# Schematic_v1_1_v8.net
KiCad netlist of a schematic drawn in EAGLE
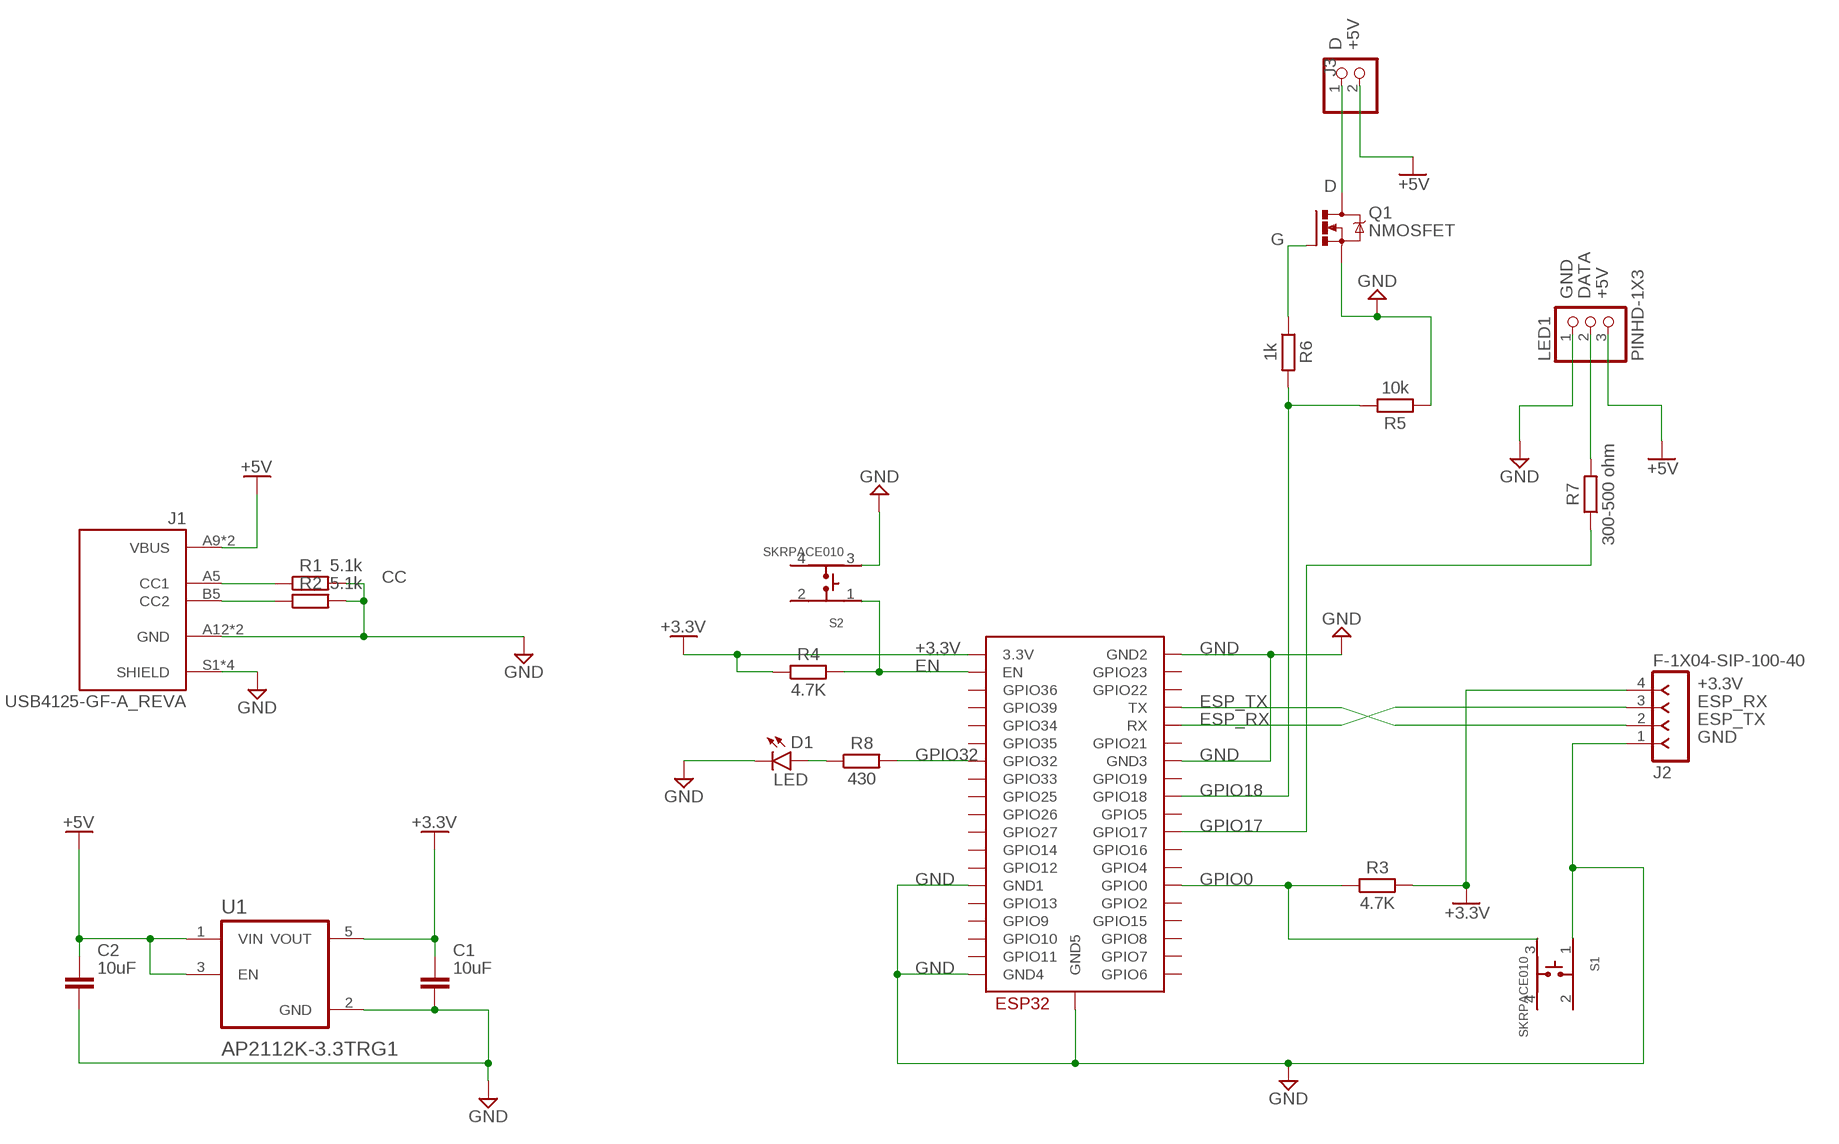
[diagram p0: schematic, sheet 1]

(export (version "E")
  (design (tool "Eeschema 10.0.6"))
  (components
    (comp (ref "C1")
      (value "10uF")
      (footprint "eagle-import:CAPC1608X85")
      (libsource (lib "eagle-import") (part "CCHIP-0603(1608-METRIC)_"))
    )
    (comp (ref "C2")
      (value "10uF")
      (footprint "eagle-import:CAPC1608X85")
      (libsource (lib "eagle-import") (part "CCHIP-0603(1608-METRIC)_"))
    )
    (comp (ref "D1")
      (value "LED")
      (footprint "eagle-import:LEDC1608X80N_FLAT-R")
      (libsource (lib "eagle-import") (part "CHIP-FLAT-R_0603-0.80MM"))
    )
    (comp (ref "J1")
      (value "USB4125-GF-A_REVA")
      (footprint "eagle-import:GCT_USB4125-GF-A_REVA")
      (fields (field (name "MF") "Global Connector Technology") (field (name "MP") "USB4125-GF-A"))
      (libsource (lib "eagle-import") (part "USB4125-GF-A_REVA"))
    )
    (comp (ref "J2")
      (value "F-1X04-SIP-100-40")
      (footprint "eagle-import:SIP-100-04-40")
      (libsource (lib "eagle-import") (part "F-1X04-SIP-100-40"))
    )
    (comp (ref "J3")
      (value "PINHD-1X2")
      (footprint "eagle-import:1X02")
      (libsource (lib "eagle-import") (part "PINHD-1X2"))
    )
    (comp (ref "LED1")
      (value "PINHD-1X3")
      (footprint "eagle-import:1X03")
      (libsource (lib "eagle-import") (part "PINHD-1X3"))
    )
    (comp (ref "Q1")
      (value "NMOSFET")
      (footprint "eagle-import:SOT23")
      (libsource (lib "eagle-import") (part "NMOSFETSOT23_"))
    )
    (comp (ref "R1")
      (value "5.1k")
      (footprint "eagle-import:RESC1608X60")
      (libsource (lib "eagle-import") (part "RCHIP-0603(1608-METRIC)_"))
    )
    (comp (ref "R2")
      (value "5.1k")
      (footprint "eagle-import:RESC1608X60")
      (libsource (lib "eagle-import") (part "RCHIP-0603(1608-METRIC)_"))
    )
    (comp (ref "R3")
      (value "4.7K")
      (footprint "eagle-import:RESC1608X60")
      (libsource (lib "eagle-import") (part "RCHIP-0603(1608-METRIC)_"))
    )
    (comp (ref "R4")
      (value "4.7K")
      (footprint "eagle-import:RESC1608X60")
      (libsource (lib "eagle-import") (part "RCHIP-0603(1608-METRIC)_"))
    )
    (comp (ref "R5")
      (value "10k")
      (footprint "eagle-import:RESC1608X60")
      (libsource (lib "eagle-import") (part "RCHIP-0603(1608-METRIC)_"))
    )
    (comp (ref "R6")
      (value "1k")
      (footprint "eagle-import:RESC1608X60")
      (libsource (lib "eagle-import") (part "RCHIP-0603(1608-METRIC)_"))
    )
    (comp (ref "R7")
      (value "300-500 ohm")
      (footprint "eagle-import:RESC1608X60")
      (libsource (lib "eagle-import") (part "RCHIP-0603(1608-METRIC)_"))
    )
    (comp (ref "R8")
      (value "430")
      (footprint "eagle-import:RESC1608X60")
      (libsource (lib "eagle-import") (part "RCHIP-0603(1608-METRIC)_"))
    )
    (comp (ref "S1")
      (value "SKRPACE010")
      (footprint "eagle-import:SW_SKRPACE010")
      (fields (field (name "MANUFACTURER") "ALPS"))
      (libsource (lib "eagle-import") (part "SKRPACE010"))
    )
    (comp (ref "S2")
      (value "SKRPACE010")
      (footprint "eagle-import:SW_SKRPACE010")
      (fields (field (name "MANUFACTURER") "ALPS"))
      (libsource (lib "eagle-import") (part "SKRPACE010"))
    )
    (comp (ref "U1")
      (value "AP2112K-3.3TRG1")
      (footprint "eagle-import:SOT95P285X140-5N")
      (fields (field (name "MANUFACTURER") "Diodes Inc."))
      (libsource (lib "eagle-import") (part "AP2112K-3.3TRG1"))
    )
    (comp (ref "U2")
      (value "ESP32-WROOM")
      (footprint "eagle-import:ESP32-WROOM")
      (libsource (lib "eagle-import") (part "ESP32-WROOM"))
    )
  )
  (nets
    (net (code "1") (name "+3.3V") (class "Default")
      (node (ref "C1") (pin "1") (pinfunction "1_1") (pintype "passive"))
      (node (ref "J2") (pin "4") (pinfunction "4_4") (pintype "passive"))
      (node (ref "R3") (pin "2") (pinfunction "2_2") (pintype "passive"))
      (node (ref "R4") (pin "1") (pinfunction "1_1") (pintype "passive"))
      (node (ref "U1") (pin "5") (pinfunction "VOUT_5") (pintype "power_in"))
      (node (ref "U2") (pin "3V3") (pinfunction "3.3V_3V3") (pintype "bidirectional"))
    )
    (net (code "2") (name "+5V") (class "Default")
      (node (ref "C2") (pin "1") (pinfunction "1_1") (pintype "passive"))
      (node (ref "J1") (pin "A9") (pinfunction "VBUS_A9") (pintype "power_in"))
      (node (ref "J1") (pin "B9") (pinfunction "VBUS_B9") (pintype "power_in"))
      (node (ref "J3") (pin "2") (pinfunction "2_2") (pintype "passive"))
      (node (ref "LED1") (pin "3") (pinfunction "3_3") (pintype "passive"))
      (node (ref "U1") (pin "1") (pinfunction "VIN_1") (pintype "power_in"))
      (node (ref "U1") (pin "3") (pinfunction "EN_3") (pintype "input"))
    )
    (net (code "3") (name "/CC") (class "Default")
      (node (ref "J1") (pin "A5") (pinfunction "CC1_A5") (pintype "bidirectional"))
      (node (ref "R1") (pin "1") (pinfunction "1_1") (pintype "passive"))
    )
    (net (code "4") (name "/D") (class "Default")
      (node (ref "J3") (pin "1") (pinfunction "1_1") (pintype "passive"))
      (node (ref "Q1") (pin "3") (pinfunction "D_3") (pintype "passive"))
    )
    (net (code "5") (name "/DATA") (class "Default")
      (node (ref "LED1") (pin "2") (pinfunction "2_2") (pintype "passive"))
      (node (ref "R7") (pin "2") (pinfunction "2_2") (pintype "passive"))
    )
    (net (code "6") (name "/EN") (class "Default")
      (node (ref "R4") (pin "2") (pinfunction "2_2") (pintype "passive"))
      (node (ref "S2") (pin "1") (pinfunction "1_1") (pintype "bidirectional"))
      (node (ref "U2") (pin "EN") (pinfunction "EN_EN") (pintype "bidirectional"))
    )
    (net (code "7") (name "/ESP_RX") (class "Default")
      (node (ref "J2") (pin "3") (pinfunction "3_3") (pintype "passive"))
      (node (ref "U2") (pin "RX") (pinfunction "RX_RX") (pintype "bidirectional"))
    )
    (net (code "8") (name "/ESP_TX") (class "Default")
      (node (ref "J2") (pin "2") (pinfunction "2_2") (pintype "passive"))
      (node (ref "U2") (pin "TX") (pinfunction "TX_TX") (pintype "bidirectional"))
    )
    (net (code "9") (name "/G") (class "Default")
      (node (ref "Q1") (pin "1") (pinfunction "G_1") (pintype "passive"))
      (node (ref "R6") (pin "1") (pinfunction "1_1") (pintype "passive"))
    )
    (net (code "10") (name "/GPIO0") (class "Default")
      (node (ref "R3") (pin "1") (pinfunction "1_1") (pintype "passive"))
      (node (ref "S1") (pin "3") (pinfunction "3_3") (pintype "bidirectional"))
      (node (ref "U2") (pin "IO0") (pinfunction "GPIO0_IO0") (pintype "bidirectional"))
    )
    (net (code "11") (name "/GPIO17") (class "Default")
      (node (ref "R7") (pin "1") (pinfunction "1_1") (pintype "passive"))
      (node (ref "U2") (pin "IO17") (pinfunction "GPIO17_IO17") (pintype "bidirectional"))
    )
    (net (code "12") (name "/GPIO18") (class "Default")
      (node (ref "R5") (pin "2") (pinfunction "2_2") (pintype "passive"))
      (node (ref "R6") (pin "2") (pinfunction "2_2") (pintype "passive"))
      (node (ref "U2") (pin "IO18") (pinfunction "GPIO18_IO18") (pintype "bidirectional"))
    )
    (net (code "13") (name "/GPIO32") (class "Default")
      (node (ref "R8") (pin "2") (pinfunction "2_2") (pintype "passive"))
      (node (ref "U2") (pin "IO32") (pinfunction "GPIO32_IO32") (pintype "bidirectional"))
    )
    (net (code "14") (name "GND") (class "Default")
      (node (ref "C1") (pin "2") (pinfunction "2_2") (pintype "passive"))
      (node (ref "C2") (pin "2") (pinfunction "2_2") (pintype "passive"))
      (node (ref "D1") (pin "C") (pinfunction "C_C") (pintype "passive"))
      (node (ref "J1") (pin "A12") (pinfunction "GND_A12") (pintype "power_in"))
      (node (ref "J1") (pin "B12") (pinfunction "GND_B12") (pintype "power_in"))
      (node (ref "J1") (pin "S1") (pinfunction "SHIELD_S1") (pintype "passive"))
      (node (ref "J1") (pin "S2") (pinfunction "SHIELD_S2") (pintype "passive"))
      (node (ref "J1") (pin "S3") (pinfunction "SHIELD_S3") (pintype "passive"))
      (node (ref "J1") (pin "S4") (pinfunction "SHIELD_S4") (pintype "passive"))
      (node (ref "J2") (pin "1") (pinfunction "1_1") (pintype "passive"))
      (node (ref "LED1") (pin "1") (pinfunction "1_1") (pintype "passive"))
      (node (ref "Q1") (pin "2") (pinfunction "S_2") (pintype "passive"))
      (node (ref "R1") (pin "2") (pinfunction "2_2") (pintype "passive"))
      (node (ref "R2") (pin "2") (pinfunction "2_2") (pintype "passive"))
      (node (ref "R5") (pin "1") (pinfunction "1_1") (pintype "passive"))
      (node (ref "S1") (pin "1") (pinfunction "1_1") (pintype "bidirectional"))
      (node (ref "S2") (pin "3") (pinfunction "3_3") (pintype "bidirectional"))
      (node (ref "U1") (pin "2") (pinfunction "GND_2") (pintype "power_in"))
      (node (ref "U2") (pin "GND1") (pinfunction "GND1_GND1") (pintype "bidirectional"))
      (node (ref "U2") (pin "GND2") (pinfunction "GND2_GND2") (pintype "bidirectional"))
      (node (ref "U2") (pin "GND3") (pinfunction "GND3_GND3") (pintype "bidirectional"))
      (node (ref "U2") (pin "GND4") (pinfunction "GND4_GND4") (pintype "bidirectional"))
      (node (ref "U2") (pin "GND5") (pinfunction "GND5_GND5") (pintype "bidirectional"))
    )
    (net (code "15") (name "Net-(D1-PadA)") (class "Default")
      (node (ref "D1") (pin "A") (pinfunction "A_A") (pintype "passive"))
      (node (ref "R8") (pin "1") (pinfunction "1_1") (pintype "passive"))
    )
    (net (code "16") (name "Net-(J1-CC2)") (class "Default")
      (node (ref "J1") (pin "B5") (pinfunction "CC2_B5") (pintype "bidirectional"))
      (node (ref "R2") (pin "1") (pinfunction "1_1") (pintype "passive"))
    )
    (net (code "17") (name "unconnected-(S1-Pad2)") (class "Default")
      (node (ref "S1") (pin "2") (pinfunction "2_2") (pintype "bidirectional"))
    )
    (net (code "18") (name "unconnected-(S1-Pad4)") (class "Default")
      (node (ref "S1") (pin "4") (pinfunction "4_4") (pintype "bidirectional"))
    )
    (net (code "19") (name "unconnected-(S2-Pad2)") (class "Default")
      (node (ref "S2") (pin "2") (pinfunction "2_2") (pintype "bidirectional"))
    )
    (net (code "20") (name "unconnected-(S2-Pad4)") (class "Default")
      (node (ref "S2") (pin "4") (pinfunction "4_4") (pintype "bidirectional"))
    )
    (net (code "21") (name "unconnected-(U2-GPIO2-PadIO2)") (class "Default")
      (node (ref "U2") (pin "IO2") (pinfunction "GPIO2_IO2") (pintype "bidirectional"))
    )
    (net (code "22") (name "unconnected-(U2-GPIO4-PadIO4)") (class "Default")
      (node (ref "U2") (pin "IO4") (pinfunction "GPIO4_IO4") (pintype "bidirectional"))
    )
    (net (code "23") (name "unconnected-(U2-GPIO5-PadIO5)") (class "Default")
      (node (ref "U2") (pin "IO5") (pinfunction "GPIO5_IO5") (pintype "bidirectional"))
    )
    (net (code "24") (name "unconnected-(U2-GPIO6-PadCLK)") (class "Default")
      (node (ref "U2") (pin "CLK") (pinfunction "GPIO6_CLK") (pintype "bidirectional"))
    )
    (net (code "25") (name "unconnected-(U2-GPIO7-PadSD0)") (class "Default")
      (node (ref "U2") (pin "SD0") (pinfunction "GPIO7_SD0") (pintype "bidirectional"))
    )
    (net (code "26") (name "unconnected-(U2-GPIO8-PadSD1)") (class "Default")
      (node (ref "U2") (pin "SD1") (pinfunction "GPIO8_SD1") (pintype "bidirectional"))
    )
    (net (code "27") (name "unconnected-(U2-GPIO9-PadSD2)") (class "Default")
      (node (ref "U2") (pin "SD2") (pinfunction "GPIO9_SD2") (pintype "bidirectional"))
    )
    (net (code "28") (name "unconnected-(U2-GPIO10-PadSD3)") (class "Default")
      (node (ref "U2") (pin "SD3") (pinfunction "GPIO10_SD3") (pintype "bidirectional"))
    )
    (net (code "29") (name "unconnected-(U2-GPIO11-PadCMD)") (class "Default")
      (node (ref "U2") (pin "CMD") (pinfunction "GPIO11_CMD") (pintype "bidirectional"))
    )
    (net (code "30") (name "unconnected-(U2-GPIO12-PadIO12)") (class "Default")
      (node (ref "U2") (pin "IO12") (pinfunction "GPIO12_IO12") (pintype "bidirectional"))
    )
    (net (code "31") (name "unconnected-(U2-GPIO13-PadIO13)") (class "Default")
      (node (ref "U2") (pin "IO13") (pinfunction "GPIO13_IO13") (pintype "bidirectional"))
    )
    (net (code "32") (name "unconnected-(U2-GPIO14-PadIO14)") (class "Default")
      (node (ref "U2") (pin "IO14") (pinfunction "GPIO14_IO14") (pintype "bidirectional"))
    )
    (net (code "33") (name "unconnected-(U2-GPIO15-PadIO15)") (class "Default")
      (node (ref "U2") (pin "IO15") (pinfunction "GPIO15_IO15") (pintype "bidirectional"))
    )
    (net (code "34") (name "unconnected-(U2-GPIO16-PadIO16)") (class "Default")
      (node (ref "U2") (pin "IO16") (pinfunction "GPIO16_IO16") (pintype "bidirectional"))
    )
    (net (code "35") (name "unconnected-(U2-GPIO19-PadIO19)") (class "Default")
      (node (ref "U2") (pin "IO19") (pinfunction "GPIO19_IO19") (pintype "bidirectional"))
    )
    (net (code "36") (name "unconnected-(U2-GPIO21-PadIO21)") (class "Default")
      (node (ref "U2") (pin "IO21") (pinfunction "GPIO21_IO21") (pintype "bidirectional"))
    )
    (net (code "37") (name "unconnected-(U2-GPIO22-PadIO22)") (class "Default")
      (node (ref "U2") (pin "IO22") (pinfunction "GPIO22_IO22") (pintype "bidirectional"))
    )
    (net (code "38") (name "unconnected-(U2-GPIO23-PadIO23)") (class "Default")
      (node (ref "U2") (pin "IO23") (pinfunction "GPIO23_IO23") (pintype "bidirectional"))
    )
    (net (code "39") (name "unconnected-(U2-GPIO25-PadIO25)") (class "Default")
      (node (ref "U2") (pin "IO25") (pinfunction "GPIO25_IO25") (pintype "bidirectional"))
    )
    (net (code "40") (name "unconnected-(U2-GPIO26-PadIO26)") (class "Default")
      (node (ref "U2") (pin "IO26") (pinfunction "GPIO26_IO26") (pintype "bidirectional"))
    )
    (net (code "41") (name "unconnected-(U2-GPIO27-PadIO27)") (class "Default")
      (node (ref "U2") (pin "IO27") (pinfunction "GPIO27_IO27") (pintype "bidirectional"))
    )
    (net (code "42") (name "unconnected-(U2-GPIO33-PadIO33)") (class "Default")
      (node (ref "U2") (pin "IO33") (pinfunction "GPIO33_IO33") (pintype "bidirectional"))
    )
    (net (code "43") (name "unconnected-(U2-GPIO34-PadIO34)") (class "Default")
      (node (ref "U2") (pin "IO34") (pinfunction "GPIO34_IO34") (pintype "bidirectional"))
    )
    (net (code "44") (name "unconnected-(U2-GPIO35-PadIO35)") (class "Default")
      (node (ref "U2") (pin "IO35") (pinfunction "GPIO35_IO35") (pintype "bidirectional"))
    )
    (net (code "45") (name "unconnected-(U2-GPIO36-PadSENSOR_VP)") (class "Default")
      (node (ref "U2") (pin "SENSOR_VP") (pinfunction "GPIO36_SENSOR_VP") (pintype "bidirectional"))
    )
    (net (code "46") (name "unconnected-(U2-GPIO39-PadSENSOR_VN)") (class "Default")
      (node (ref "U2") (pin "SENSOR_VN") (pinfunction "GPIO39_SENSOR_VN") (pintype "bidirectional"))
    )
  )
)
